# IR_emitter_perf.net
KiCad netlist of a schematic drawn in EAGLE
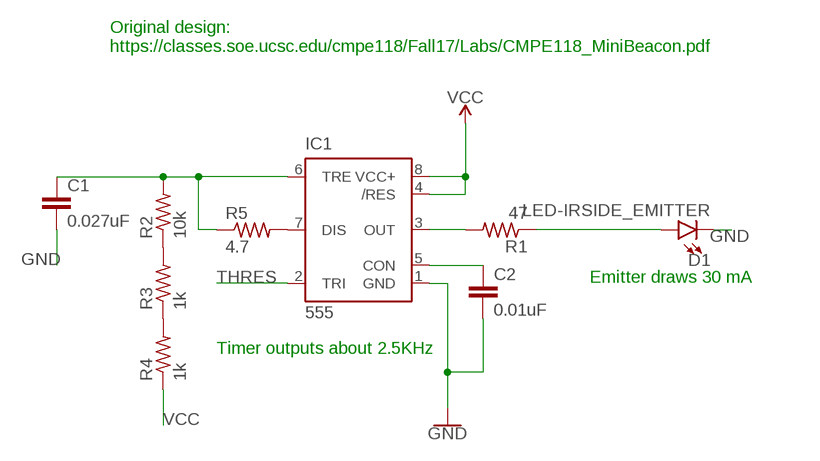
[diagram p0: schematic, sheet 1]

(export (version "E")
  (design (tool "Eeschema 10.0.6"))
  (components
    (comp (ref "C1")
      (value "0.027uF")
      (footprint "eagle-import:C025-024X044")
      (libsource (lib "eagle-import") (part "C-EU025-024X044"))
    )
    (comp (ref "C2")
      (value "0.01uF")
      (footprint "eagle-import:C025-024X044")
      (libsource (lib "eagle-import") (part "C-EU025-024X044"))
    )
    (comp (ref "D1")
      (value "LED-IRSIDE_EMITTER")
      (footprint "eagle-import:LTE-302")
      (libsource (lib "eagle-import") (part "LED-IRSIDE_EMITTER"))
    )
    (comp (ref "IC1")
      (value "555")
      (footprint "eagle-import:DIP08")
      (libsource (lib "eagle-import") (part "555P"))
    )
    (comp (ref "R1")
      (value "47")
      (footprint "eagle-import:0204V")
      (libsource (lib "eagle-import") (part "R-US_0204/2V"))
    )
    (comp (ref "R2")
      (value "10k")
      (footprint "eagle-import:0204V")
      (libsource (lib "eagle-import") (part "R-US_0204/2V"))
    )
    (comp (ref "R3")
      (value "1k")
      (footprint "eagle-import:0204V")
      (libsource (lib "eagle-import") (part "R-US_0204/2V"))
    )
    (comp (ref "R4")
      (value "1k")
      (footprint "eagle-import:0204V")
      (libsource (lib "eagle-import") (part "R-US_0204/2V"))
    )
    (comp (ref "R5")
      (value "4.7")
      (footprint "eagle-import:0204V")
      (libsource (lib "eagle-import") (part "R-US_0204/2V"))
    )
  )
  (nets
    (net (code "1") (name "/THRES") (class "Default")
      (node (ref "C1") (pin "1") (pinfunction "1_1") (pintype "passive"))
      (node (ref "IC1") (pin "2") (pinfunction "TRI_2") (pintype "input"))
      (node (ref "IC1") (pin "6") (pinfunction "TRE_6") (pintype "input"))
      (node (ref "R2") (pin "2") (pinfunction "2_2") (pintype "passive"))
      (node (ref "R5") (pin "1") (pinfunction "1_1") (pintype "passive"))
    )
    (net (code "2") (name "GND") (class "Default")
      (node (ref "C1") (pin "2") (pinfunction "2_2") (pintype "passive"))
      (node (ref "C2") (pin "2") (pinfunction "2_2") (pintype "passive"))
      (node (ref "D1") (pin "C") (pinfunction "C_C") (pintype "passive"))
      (node (ref "IC1") (pin "1") (pinfunction "GND_1") (pintype "power_in"))
    )
    (net (code "3") (name "Net-(D1-PadA)") (class "Default")
      (node (ref "D1") (pin "A") (pinfunction "A_A") (pintype "passive"))
      (node (ref "R1") (pin "1") (pinfunction "1_1") (pintype "passive"))
    )
    (net (code "4") (name "Net-(IC1-CON)") (class "Default")
      (node (ref "C2") (pin "1") (pinfunction "1_1") (pintype "passive"))
      (node (ref "IC1") (pin "5") (pinfunction "CON_5") (pintype "input"))
    )
    (net (code "5") (name "Net-(IC1-DIS)") (class "Default")
      (node (ref "IC1") (pin "7") (pinfunction "DIS_7") (pintype "input"))
      (node (ref "R5") (pin "2") (pinfunction "2_2") (pintype "passive"))
    )
    (net (code "6") (name "Net-(IC1-OUT)") (class "Default")
      (node (ref "IC1") (pin "3") (pinfunction "OUT_3") (pintype "output"))
      (node (ref "R1") (pin "2") (pinfunction "2_2") (pintype "passive"))
    )
    (net (code "7") (name "Net-(R2-Pad1)") (class "Default")
      (node (ref "R2") (pin "1") (pinfunction "1_1") (pintype "passive"))
      (node (ref "R3") (pin "2") (pinfunction "2_2") (pintype "passive"))
    )
    (net (code "8") (name "Net-(R3-Pad1)") (class "Default")
      (node (ref "R3") (pin "1") (pinfunction "1_1") (pintype "passive"))
      (node (ref "R4") (pin "2") (pinfunction "2_2") (pintype "passive"))
    )
    (net (code "9") (name "VCC") (class "Default")
      (node (ref "IC1") (pin "4") (pinfunction "/RES_4") (pintype "input"))
      (node (ref "IC1") (pin "8") (pinfunction "VCC+_8") (pintype "power_in"))
      (node (ref "R4") (pin "1") (pinfunction "1_1") (pintype "passive"))
    )
  )
)
